# frontpanelboard.net
KiCad netlist of a schematic drawn in EAGLE
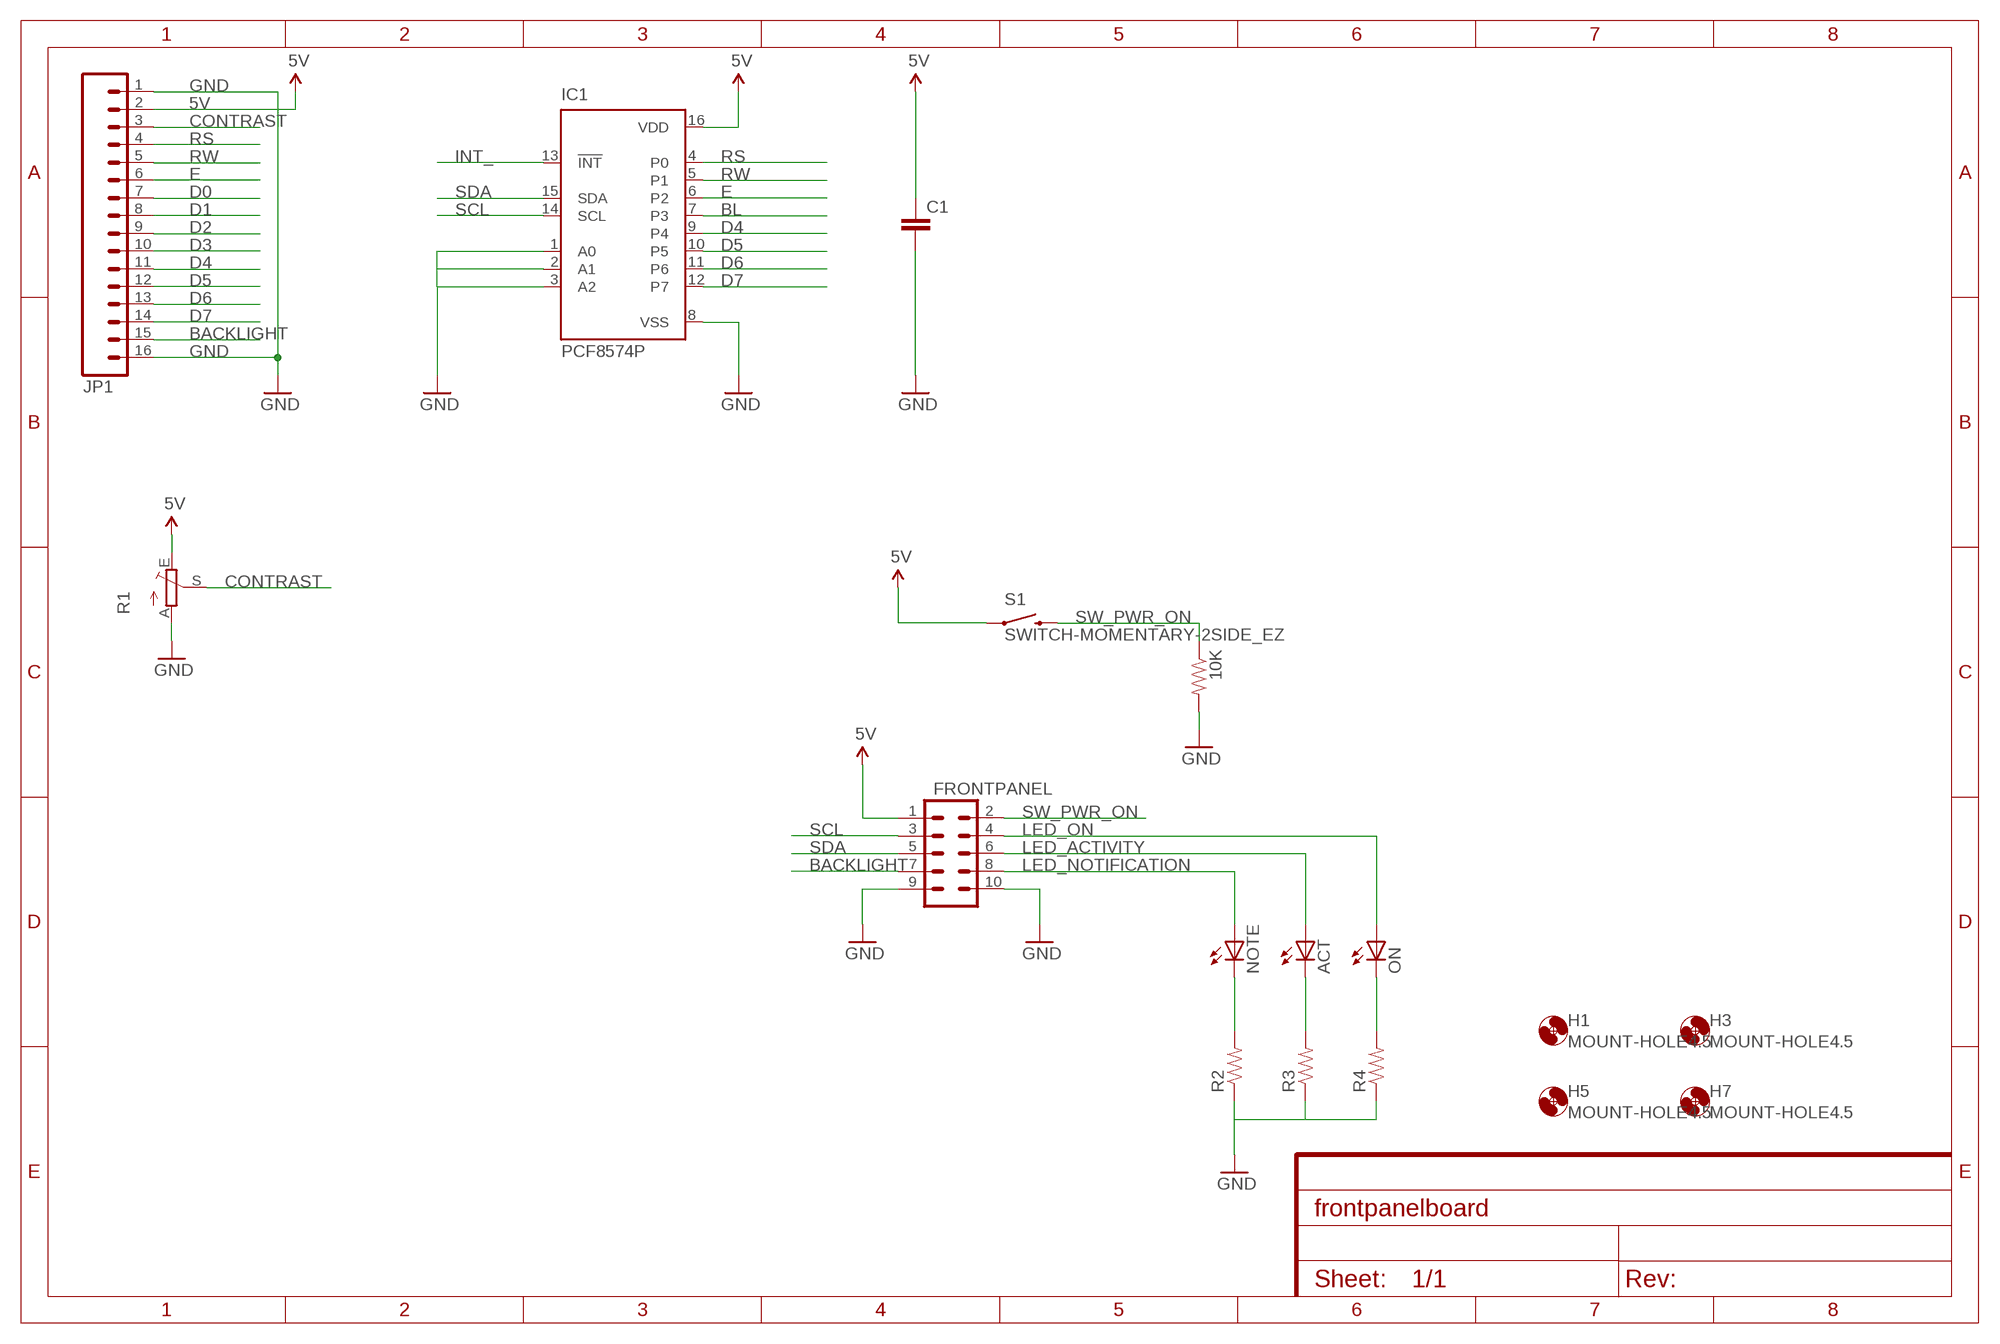
[diagram p0: schematic, sheet 1]

(export (version "E")
  (design (tool "Eeschema 10.0.6"))
  (components
    (comp (ref "10K")
      (value "RESISTOREZ")
      (footprint "eagle-import:AXIAL-0.3EZ")
      (libsource (lib "eagle-import") (part "RESISTOREZ"))
    )
    (comp (ref "ACT")
      (value "LEDB155")
      (footprint "eagle-import:Q62902-B155")
      (libsource (lib "eagle-import") (part "LEDB155"))
    )
    (comp (ref "C1")
      (value "CAPEZ")
      (footprint "eagle-import:CAP-PTH-SMALLEZ")
      (libsource (lib "eagle-import") (part "CAPEZ"))
    )
    (comp (ref "FRONTPANEL")
      (value "M05X2SHD_LOCK")
      (footprint "eagle-import:2X5-SHROUDED_LOCK")
      (libsource (lib "eagle-import") (part "M05X2SHD_LOCK"))
    )
    (comp (ref "H1")
      (value "MOUNT-HOLE4.5")
      (footprint "eagle-import:4,5")
      (libsource (lib "eagle-import") (part "MOUNT-HOLE4.5"))
    )
    (comp (ref "H3")
      (value "MOUNT-HOLE4.5")
      (footprint "eagle-import:4,5")
      (libsource (lib "eagle-import") (part "MOUNT-HOLE4.5"))
    )
    (comp (ref "H5")
      (value "MOUNT-HOLE4.5")
      (footprint "eagle-import:4,5")
      (libsource (lib "eagle-import") (part "MOUNT-HOLE4.5"))
    )
    (comp (ref "H7")
      (value "MOUNT-HOLE4.5")
      (footprint "eagle-import:4,5")
      (libsource (lib "eagle-import") (part "MOUNT-HOLE4.5"))
    )
    (comp (ref "IC1")
      (value "PCF8574P")
      (footprint "eagle-import:DIL16")
      (fields (field (name "MPN") "PCF8574PN"))
      (libsource (lib "eagle-import") (part "PCF8574P"))
    )
    (comp (ref "JP1")
      (value "M16LONGPADS")
      (footprint "eagle-import:1X16_LONGPADS")
      (libsource (lib "eagle-import") (part "M16LONGPADS"))
    )
    (comp (ref "NOTE")
      (value "LEDB155")
      (footprint "eagle-import:Q62902-B155")
      (libsource (lib "eagle-import") (part "LEDB155"))
    )
    (comp (ref "ON")
      (value "LEDB155")
      (footprint "eagle-import:Q62902-B155")
      (libsource (lib "eagle-import") (part "LEDB155"))
    )
    (comp (ref "R1")
      (value "TRIM_EU-LI10")
      (footprint "eagle-import:LI10")
      (libsource (lib "eagle-import") (part "TRIM_EU-LI10"))
    )
    (comp (ref "R2")
      (value "RESISTOREZ")
      (footprint "eagle-import:AXIAL-0.3EZ")
      (libsource (lib "eagle-import") (part "RESISTOREZ"))
    )
    (comp (ref "R3")
      (value "RESISTOREZ")
      (footprint "eagle-import:AXIAL-0.3EZ")
      (libsource (lib "eagle-import") (part "RESISTOREZ"))
    )
    (comp (ref "R4")
      (value "RESISTOREZ")
      (footprint "eagle-import:AXIAL-0.3EZ")
      (libsource (lib "eagle-import") (part "RESISTOREZ"))
    )
    (comp (ref "S1")
      (value "SWITCH-MOMENTARY-2SIDE_EZ")
      (footprint "eagle-import:TACTILE-PTH-SIDEEZ")
      (libsource (lib "eagle-import") (part "SWITCH-MOMENTARY-2SIDE_EZ"))
    )
  )
  (nets
    (net (code "1") (name "/BACKLIGHT") (class "Default")
      (node (ref "FRONTPANEL") (pin "7") (pinfunction "7_7") (pintype "passive"))
      (node (ref "JP1") (pin "15") (pinfunction "15_15") (pintype "passive"))
    )
    (net (code "2") (name "/BL") (class "Default")
      (node (ref "IC1") (pin "7") (pinfunction "P3_7") (pintype "bidirectional"))
    )
    (net (code "3") (name "/CONTRAST") (class "Default")
      (node (ref "JP1") (pin "3") (pinfunction "3_3") (pintype "passive"))
      (node (ref "R1") (pin "S") (pinfunction "S_S") (pintype "passive"))
    )
    (net (code "4") (name "/D0") (class "Default")
      (node (ref "JP1") (pin "7") (pinfunction "7_7") (pintype "passive"))
    )
    (net (code "5") (name "/D1") (class "Default")
      (node (ref "JP1") (pin "8") (pinfunction "8_8") (pintype "passive"))
    )
    (net (code "6") (name "/D2") (class "Default")
      (node (ref "JP1") (pin "9") (pinfunction "9_9") (pintype "passive"))
    )
    (net (code "7") (name "/D3") (class "Default")
      (node (ref "JP1") (pin "10") (pinfunction "10_10") (pintype "passive"))
    )
    (net (code "8") (name "/D4") (class "Default")
      (node (ref "IC1") (pin "9") (pinfunction "P4_9") (pintype "bidirectional"))
      (node (ref "JP1") (pin "11") (pinfunction "11_11") (pintype "passive"))
    )
    (net (code "9") (name "/D5") (class "Default")
      (node (ref "IC1") (pin "10") (pinfunction "P5_10") (pintype "bidirectional"))
      (node (ref "JP1") (pin "12") (pinfunction "12_12") (pintype "passive"))
    )
    (net (code "10") (name "/D6") (class "Default")
      (node (ref "IC1") (pin "11") (pinfunction "P6_11") (pintype "bidirectional"))
      (node (ref "JP1") (pin "13") (pinfunction "13_13") (pintype "passive"))
    )
    (net (code "11") (name "/D7") (class "Default")
      (node (ref "IC1") (pin "12") (pinfunction "P7_12") (pintype "bidirectional"))
      (node (ref "JP1") (pin "14") (pinfunction "14_14") (pintype "passive"))
    )
    (net (code "12") (name "/E") (class "Default")
      (node (ref "IC1") (pin "6") (pinfunction "P2_6") (pintype "bidirectional"))
      (node (ref "JP1") (pin "6") (pinfunction "6_6") (pintype "passive"))
    )
    (net (code "13") (name "/INT_") (class "Default")
      (node (ref "IC1") (pin "13") (pinfunction "~{INT}_13") (pintype "output"))
    )
    (net (code "14") (name "/LED_ACTIVITY") (class "Default")
      (node (ref "ACT") (pin "A") (pinfunction "A_A") (pintype "passive"))
      (node (ref "FRONTPANEL") (pin "6") (pinfunction "6_6") (pintype "passive"))
    )
    (net (code "15") (name "/LED_NOTIFICATION") (class "Default")
      (node (ref "FRONTPANEL") (pin "8") (pinfunction "8_8") (pintype "passive"))
      (node (ref "NOTE") (pin "A") (pinfunction "A_A") (pintype "passive"))
    )
    (net (code "16") (name "/LED_ON") (class "Default")
      (node (ref "FRONTPANEL") (pin "4") (pinfunction "4_4") (pintype "passive"))
      (node (ref "ON") (pin "A") (pinfunction "A_A") (pintype "passive"))
    )
    (net (code "17") (name "/RS") (class "Default")
      (node (ref "IC1") (pin "4") (pinfunction "P0_4") (pintype "bidirectional"))
      (node (ref "JP1") (pin "4") (pinfunction "4_4") (pintype "passive"))
    )
    (net (code "18") (name "/RW") (class "Default")
      (node (ref "IC1") (pin "5") (pinfunction "P1_5") (pintype "bidirectional"))
      (node (ref "JP1") (pin "5") (pinfunction "5_5") (pintype "passive"))
    )
    (net (code "19") (name "/SCL") (class "Default")
      (node (ref "FRONTPANEL") (pin "3") (pinfunction "3_3") (pintype "passive"))
      (node (ref "IC1") (pin "14") (pinfunction "SCL_14") (pintype "input"))
    )
    (net (code "20") (name "/SDA") (class "Default")
      (node (ref "FRONTPANEL") (pin "5") (pinfunction "5_5") (pintype "passive"))
      (node (ref "IC1") (pin "15") (pinfunction "SDA_15") (pintype "bidirectional"))
    )
    (net (code "21") (name "/SW_PWR_ON") (class "Default")
      (node (ref "10K") (pin "P$1") (pinfunction "1_P$1") (pintype "passive"))
      (node (ref "FRONTPANEL") (pin "2") (pinfunction "2_2") (pintype "passive"))
      (node (ref "S1") (pin "2") (pinfunction "2_2") (pintype "passive"))
    )
    (net (code "22") (name "5V") (class "Default")
      (node (ref "C1") (pin "1") (pinfunction "1_1") (pintype "passive"))
      (node (ref "FRONTPANEL") (pin "1") (pinfunction "1_1") (pintype "passive"))
      (node (ref "IC1") (pin "16") (pinfunction "VDD_16") (pintype "power_in"))
      (node (ref "JP1") (pin "2") (pinfunction "2_2") (pintype "passive"))
      (node (ref "R1") (pin "E") (pinfunction "E_E") (pintype "passive"))
      (node (ref "S1") (pin "1") (pinfunction "1_1") (pintype "passive"))
    )
    (net (code "23") (name "GND") (class "Default")
      (node (ref "10K") (pin "P$2") (pinfunction "2_P$2") (pintype "passive"))
      (node (ref "C1") (pin "2") (pinfunction "2_2") (pintype "passive"))
      (node (ref "FRONTPANEL") (pin "10") (pinfunction "10_10") (pintype "passive"))
      (node (ref "FRONTPANEL") (pin "9") (pinfunction "9_9") (pintype "passive"))
      (node (ref "IC1") (pin "1") (pinfunction "A0_1") (pintype "input"))
      (node (ref "IC1") (pin "2") (pinfunction "A1_2") (pintype "input"))
      (node (ref "IC1") (pin "3") (pinfunction "A2_3") (pintype "input"))
      (node (ref "IC1") (pin "8") (pinfunction "VSS_8") (pintype "power_in"))
      (node (ref "JP1") (pin "1") (pinfunction "1_1") (pintype "passive"))
      (node (ref "JP1") (pin "16") (pinfunction "16_16") (pintype "passive"))
      (node (ref "R1") (pin "A") (pinfunction "A_A") (pintype "passive"))
      (node (ref "R2") (pin "P$1") (pinfunction "1_P$1") (pintype "passive"))
      (node (ref "R3") (pin "P$1") (pinfunction "1_P$1") (pintype "passive"))
      (node (ref "R4") (pin "P$1") (pinfunction "1_P$1") (pintype "passive"))
    )
    (net (code "24") (name "Net-(ACT-C)") (class "Default")
      (node (ref "ACT") (pin "K") (pinfunction "C_K") (pintype "passive"))
      (node (ref "R3") (pin "P$2") (pinfunction "2_P$2") (pintype "passive"))
    )
    (net (code "25") (name "Net-(NOTE-C)") (class "Default")
      (node (ref "NOTE") (pin "K") (pinfunction "C_K") (pintype "passive"))
      (node (ref "R2") (pin "P$2") (pinfunction "2_P$2") (pintype "passive"))
    )
    (net (code "26") (name "Net-(ON-C)") (class "Default")
      (node (ref "ON") (pin "K") (pinfunction "C_K") (pintype "passive"))
      (node (ref "R4") (pin "P$2") (pinfunction "2_P$2") (pintype "passive"))
    )
  )
)
